# open-bldc-powermini.net
KiCad netlist of a schematic drawn in EAGLE
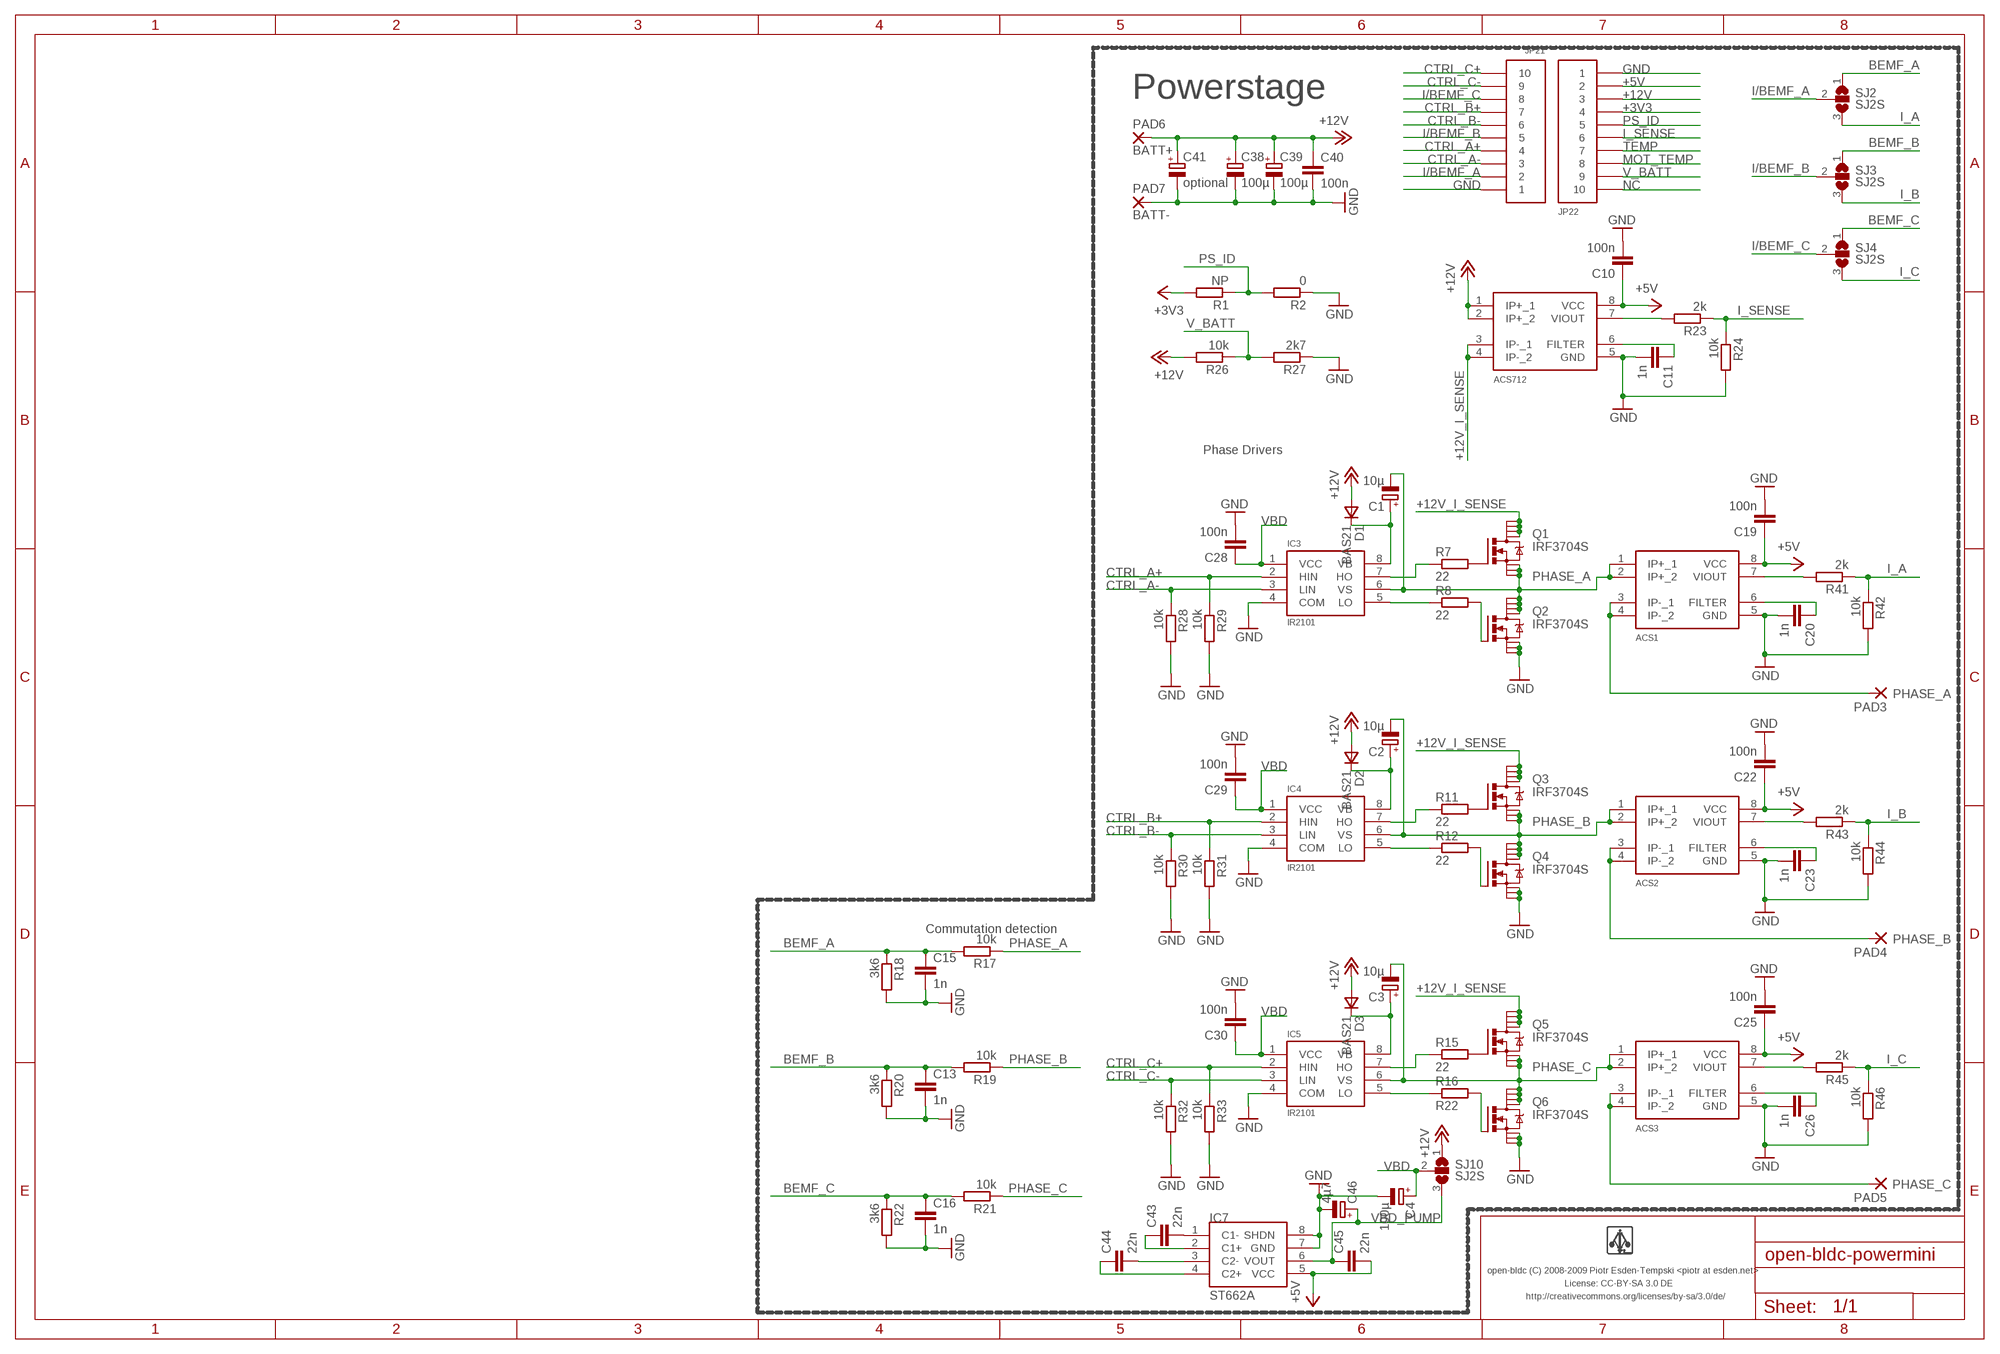
[diagram p0: schematic, sheet 1]

(export (version "E")
  (design (tool "Eeschema 10.0.6"))
  (components
    (comp (ref "ACS1")
      (value "ACS712")
      (footprint "eagle-import:SO8")
      (libsource (lib "eagle-import") (part "ACS712"))
    )
    (comp (ref "ACS2")
      (value "ACS712")
      (footprint "eagle-import:SO8")
      (libsource (lib "eagle-import") (part "ACS712"))
    )
    (comp (ref "ACS3")
      (value "ACS712")
      (footprint "eagle-import:SO8")
      (libsource (lib "eagle-import") (part "ACS712"))
    )
    (comp (ref "ACS712")
      (value "ACS712")
      (footprint "eagle-import:SO8")
      (libsource (lib "eagle-import") (part "ACS712"))
    )
    (comp (ref "C1")
      (value "10µ")
      (footprint "eagle-import:A_3216-18R")
      (libsource (lib "eagle-import") (part "CPOL-EUA/3216-18R"))
    )
    (comp (ref "C2")
      (value "10µ")
      (footprint "eagle-import:A_3216-18R")
      (libsource (lib "eagle-import") (part "CPOL-EUA/3216-18R"))
    )
    (comp (ref "C3")
      (value "10µ")
      (footprint "eagle-import:A_3216-18R")
      (libsource (lib "eagle-import") (part "CPOL-EUA/3216-18R"))
    )
    (comp (ref "C4")
      (value "100µ")
      (footprint "eagle-import:D_7343-31R")
      (libsource (lib "eagle-import") (part "CPOL-EUD/7343-31R"))
    )
    (comp (ref "C10")
      (value "100n")
      (footprint "eagle-import:C0603")
      (libsource (lib "eagle-import") (part "C-EUC0603"))
    )
    (comp (ref "C11")
      (value "1n")
      (footprint "eagle-import:C0603")
      (libsource (lib "eagle-import") (part "C-EUC0603"))
    )
    (comp (ref "C13")
      (value "1n")
      (footprint "eagle-import:C0603")
      (libsource (lib "eagle-import") (part "C-EUC0603"))
    )
    (comp (ref "C15")
      (value "1n")
      (footprint "eagle-import:C0603")
      (libsource (lib "eagle-import") (part "C-EUC0603"))
    )
    (comp (ref "C16")
      (value "1n")
      (footprint "eagle-import:C0603")
      (libsource (lib "eagle-import") (part "C-EUC0603"))
    )
    (comp (ref "C19")
      (value "100n")
      (footprint "eagle-import:C0603")
      (libsource (lib "eagle-import") (part "C-EUC0603"))
    )
    (comp (ref "C20")
      (value "1n")
      (footprint "eagle-import:C0603")
      (libsource (lib "eagle-import") (part "C-EUC0603"))
    )
    (comp (ref "C22")
      (value "100n")
      (footprint "eagle-import:C0603")
      (libsource (lib "eagle-import") (part "C-EUC0603"))
    )
    (comp (ref "C23")
      (value "1n")
      (footprint "eagle-import:C0603")
      (libsource (lib "eagle-import") (part "C-EUC0603"))
    )
    (comp (ref "C25")
      (value "100n")
      (footprint "eagle-import:C0603")
      (libsource (lib "eagle-import") (part "C-EUC0603"))
    )
    (comp (ref "C26")
      (value "1n")
      (footprint "eagle-import:C0603")
      (libsource (lib "eagle-import") (part "C-EUC0603"))
    )
    (comp (ref "C28")
      (value "100n")
      (footprint "eagle-import:C0603")
      (libsource (lib "eagle-import") (part "C-EUC0603"))
    )
    (comp (ref "C29")
      (value "100n")
      (footprint "eagle-import:C0603")
      (libsource (lib "eagle-import") (part "C-EUC0603"))
    )
    (comp (ref "C30")
      (value "100n")
      (footprint "eagle-import:C0603")
      (libsource (lib "eagle-import") (part "C-EUC0603"))
    )
    (comp (ref "C38")
      (value "100µ")
      (footprint "eagle-import:D_7343-31R")
      (libsource (lib "eagle-import") (part "CPOL-EUD/7343-31R"))
    )
    (comp (ref "C39")
      (value "100µ")
      (footprint "eagle-import:D_7343-31R")
      (libsource (lib "eagle-import") (part "CPOL-EUD/7343-31R"))
    )
    (comp (ref "C40")
      (value "100n")
      (footprint "eagle-import:C0603")
      (libsource (lib "eagle-import") (part "C-EUC0603"))
    )
    (comp (ref "C41")
      (value "optional")
      (footprint "eagle-import:E5-6")
      (libsource (lib "eagle-import") (part "CPOL-EUE5-6"))
    )
    (comp (ref "C43")
      (value "22n")
      (footprint "eagle-import:C0603")
      (libsource (lib "eagle-import") (part "C-EUC0603"))
    )
    (comp (ref "C44")
      (value "22n")
      (footprint "eagle-import:C0603")
      (libsource (lib "eagle-import") (part "C-EUC0603"))
    )
    (comp (ref "C45")
      (value "22n")
      (footprint "eagle-import:C0603")
      (libsource (lib "eagle-import") (part "C-EUC0603"))
    )
    (comp (ref "C46")
      (value "4µ7")
      (footprint "eagle-import:A_3216-18R")
      (libsource (lib "eagle-import") (part "CPOL-EUA/3216-18R"))
    )
    (comp (ref "D1")
      (value "BAS21")
      (footprint "eagle-import:SOT-23")
      (libsource (lib "eagle-import") (part "VAR2SOT23"))
    )
    (comp (ref "D2")
      (value "BAS21")
      (footprint "eagle-import:SOT-23")
      (libsource (lib "eagle-import") (part "VAR2SOT23"))
    )
    (comp (ref "D3")
      (value "BAS21")
      (footprint "eagle-import:SOT-23")
      (libsource (lib "eagle-import") (part "VAR2SOT23"))
    )
    (comp (ref "IC3")
      (value "IR2101")
      (footprint "eagle-import:SO-8")
      (libsource (lib "eagle-import") (part "IR2101"))
    )
    (comp (ref "IC4")
      (value "IR2101")
      (footprint "eagle-import:SO-8")
      (libsource (lib "eagle-import") (part "IR2101"))
    )
    (comp (ref "IC5")
      (value "IR2101")
      (footprint "eagle-import:SO-8")
      (libsource (lib "eagle-import") (part "IR2101"))
    )
    (comp (ref "IC7")
      (value "ST662A")
      (footprint "eagle-import:SO8")
      (libsource (lib "eagle-import") (part "ST662A"))
    )
    (comp (ref "JP21")
      (value "PIN_HDR_1.27MM_10")
      (footprint "eagle-import:PIN_HDR_1.27MM_SMD_10")
      (libsource (lib "eagle-import") (part "PIN_HDR_1.27MM_10_SMT"))
    )
    (comp (ref "JP22")
      (value "PIN_HDR_1.27MM_10")
      (footprint "eagle-import:PIN_HDR_1.27MM_SMD_10")
      (libsource (lib "eagle-import") (part "PIN_HDR_1.27MM_10_SMT"))
    )
    (comp (ref "PAD3")
      (value "PHASE_A")
      (footprint "eagle-import:SMD2,54-5,08")
      (libsource (lib "eagle-import") (part "SMD5"))
    )
    (comp (ref "PAD4")
      (value "PHASE_B")
      (footprint "eagle-import:SMD2,54-5,08")
      (libsource (lib "eagle-import") (part "SMD5"))
    )
    (comp (ref "PAD5")
      (value "PHASE_C")
      (footprint "eagle-import:SMD2,54-5,08")
      (libsource (lib "eagle-import") (part "SMD5"))
    )
    (comp (ref "PAD6")
      (value "BATT+")
      (footprint "eagle-import:SMD2,54-5,08")
      (libsource (lib "eagle-import") (part "SMD5"))
    )
    (comp (ref "PAD7")
      (value "BATT-")
      (footprint "eagle-import:SMD2,54-5,08")
      (libsource (lib "eagle-import") (part "SMD5"))
    )
    (comp (ref "Q1")
      (value "IRF3704S")
      (footprint "eagle-import:SO-08")
      (libsource (lib "eagle-import") (part "N-MOSFET-SO8S"))
    )
    (comp (ref "Q2")
      (value "IRF3704S")
      (footprint "eagle-import:SO-08")
      (libsource (lib "eagle-import") (part "N-MOSFET-SO8S"))
    )
    (comp (ref "Q3")
      (value "IRF3704S")
      (footprint "eagle-import:SO-08")
      (libsource (lib "eagle-import") (part "N-MOSFET-SO8S"))
    )
    (comp (ref "Q4")
      (value "IRF3704S")
      (footprint "eagle-import:SO-08")
      (libsource (lib "eagle-import") (part "N-MOSFET-SO8S"))
    )
    (comp (ref "Q5")
      (value "IRF3704S")
      (footprint "eagle-import:SO-08")
      (libsource (lib "eagle-import") (part "N-MOSFET-SO8S"))
    )
    (comp (ref "Q6")
      (value "IRF3704S")
      (footprint "eagle-import:SO-08")
      (libsource (lib "eagle-import") (part "N-MOSFET-SO8S"))
    )
    (comp (ref "R1")
      (value "NP")
      (footprint "eagle-import:R0603")
      (libsource (lib "eagle-import") (part "R-EU_R0603"))
    )
    (comp (ref "R2")
      (value "0")
      (footprint "eagle-import:R0603")
      (libsource (lib "eagle-import") (part "R-EU_R0603"))
    )
    (comp (ref "R7")
      (value "22")
      (footprint "eagle-import:R0603")
      (libsource (lib "eagle-import") (part "R-EU_R0603"))
    )
    (comp (ref "R8")
      (value "22")
      (footprint "eagle-import:R0603")
      (libsource (lib "eagle-import") (part "R-EU_R0603"))
    )
    (comp (ref "R11")
      (value "22")
      (footprint "eagle-import:R0603")
      (libsource (lib "eagle-import") (part "R-EU_R0603"))
    )
    (comp (ref "R12")
      (value "22")
      (footprint "eagle-import:R0603")
      (libsource (lib "eagle-import") (part "R-EU_R0603"))
    )
    (comp (ref "R15")
      (value "22")
      (footprint "eagle-import:R0603")
      (libsource (lib "eagle-import") (part "R-EU_R0603"))
    )
    (comp (ref "R16")
      (value "R22")
      (footprint "eagle-import:R0603")
      (libsource (lib "eagle-import") (part "R-EU_R0603"))
    )
    (comp (ref "R17")
      (value "10k")
      (footprint "eagle-import:R0603")
      (libsource (lib "eagle-import") (part "R-EU_R0603"))
    )
    (comp (ref "R18")
      (value "3k6")
      (footprint "eagle-import:R0603")
      (libsource (lib "eagle-import") (part "R-EU_R0603"))
    )
    (comp (ref "R19")
      (value "10k")
      (footprint "eagle-import:R0603")
      (libsource (lib "eagle-import") (part "R-EU_R0603"))
    )
    (comp (ref "R20")
      (value "3k6")
      (footprint "eagle-import:R0603")
      (libsource (lib "eagle-import") (part "R-EU_R0603"))
    )
    (comp (ref "R21")
      (value "10k")
      (footprint "eagle-import:R0603")
      (libsource (lib "eagle-import") (part "R-EU_R0603"))
    )
    (comp (ref "R22")
      (value "3k6")
      (footprint "eagle-import:R0603")
      (libsource (lib "eagle-import") (part "R-EU_R0603"))
    )
    (comp (ref "R23")
      (value "2k")
      (footprint "eagle-import:R0603")
      (libsource (lib "eagle-import") (part "R-EU_R0603"))
    )
    (comp (ref "R24")
      (value "10k")
      (footprint "eagle-import:R0603")
      (libsource (lib "eagle-import") (part "R-EU_R0603"))
    )
    (comp (ref "R26")
      (value "10k")
      (footprint "eagle-import:R0603")
      (libsource (lib "eagle-import") (part "R-EU_R0603"))
    )
    (comp (ref "R27")
      (value "2k7")
      (footprint "eagle-import:R0603")
      (libsource (lib "eagle-import") (part "R-EU_R0603"))
    )
    (comp (ref "R28")
      (value "10k")
      (footprint "eagle-import:R0603")
      (libsource (lib "eagle-import") (part "R-EU_R0603"))
    )
    (comp (ref "R29")
      (value "10k")
      (footprint "eagle-import:R0603")
      (libsource (lib "eagle-import") (part "R-EU_R0603"))
    )
    (comp (ref "R30")
      (value "10k")
      (footprint "eagle-import:R0603")
      (libsource (lib "eagle-import") (part "R-EU_R0603"))
    )
    (comp (ref "R31")
      (value "10k")
      (footprint "eagle-import:R0603")
      (libsource (lib "eagle-import") (part "R-EU_R0603"))
    )
    (comp (ref "R32")
      (value "10k")
      (footprint "eagle-import:R0603")
      (libsource (lib "eagle-import") (part "R-EU_R0603"))
    )
    (comp (ref "R33")
      (value "10k")
      (footprint "eagle-import:R0603")
      (libsource (lib "eagle-import") (part "R-EU_R0603"))
    )
    (comp (ref "R41")
      (value "2k")
      (footprint "eagle-import:R0603")
      (libsource (lib "eagle-import") (part "R-EU_R0603"))
    )
    (comp (ref "R42")
      (value "10k")
      (footprint "eagle-import:R0603")
      (libsource (lib "eagle-import") (part "R-EU_R0603"))
    )
    (comp (ref "R43")
      (value "2k")
      (footprint "eagle-import:R0603")
      (libsource (lib "eagle-import") (part "R-EU_R0603"))
    )
    (comp (ref "R44")
      (value "10k")
      (footprint "eagle-import:R0603")
      (libsource (lib "eagle-import") (part "R-EU_R0603"))
    )
    (comp (ref "R45")
      (value "2k")
      (footprint "eagle-import:R0603")
      (libsource (lib "eagle-import") (part "R-EU_R0603"))
    )
    (comp (ref "R46")
      (value "10k")
      (footprint "eagle-import:R0603")
      (libsource (lib "eagle-import") (part "R-EU_R0603"))
    )
    (comp (ref "SJ2")
      (value "SJ2S")
      (footprint "eagle-import:SJ2S")
      (libsource (lib "eagle-import") (part "SJ2S"))
    )
    (comp (ref "SJ3")
      (value "SJ2S")
      (footprint "eagle-import:SJ2S")
      (libsource (lib "eagle-import") (part "SJ2S"))
    )
    (comp (ref "SJ4")
      (value "SJ2S")
      (footprint "eagle-import:SJ2S")
      (libsource (lib "eagle-import") (part "SJ2S"))
    )
    (comp (ref "SJ10")
      (value "SJ2S")
      (footprint "eagle-import:SJ2S")
      (libsource (lib "eagle-import") (part "SJ2S"))
    )
  )
  (nets
    (net (code "1") (name "+3V3") (class "Default")
      (node (ref "JP22") (pin "4") (pinfunction "4_4") (pintype "bidirectional"))
      (node (ref "R1") (pin "2") (pinfunction "2_2") (pintype "passive"))
    )
    (net (code "2") (name "+5V") (class "Default")
      (node (ref "ACS1") (pin "8") (pinfunction "VCC_8") (pintype "bidirectional"))
      (node (ref "ACS2") (pin "8") (pinfunction "VCC_8") (pintype "bidirectional"))
      (node (ref "ACS3") (pin "8") (pinfunction "VCC_8") (pintype "bidirectional"))
      (node (ref "ACS712") (pin "8") (pinfunction "VCC_8") (pintype "bidirectional"))
      (node (ref "C10") (pin "1") (pinfunction "1_1") (pintype "passive"))
      (node (ref "C19") (pin "1") (pinfunction "1_1") (pintype "passive"))
      (node (ref "C22") (pin "1") (pinfunction "1_1") (pintype "passive"))
      (node (ref "C25") (pin "1") (pinfunction "1_1") (pintype "passive"))
      (node (ref "C45") (pin "2") (pinfunction "2_2") (pintype "passive"))
      (node (ref "IC7") (pin "5") (pinfunction "VCC_5") (pintype "bidirectional"))
      (node (ref "JP22") (pin "2") (pinfunction "2_2") (pintype "bidirectional"))
    )
    (net (code "3") (name "+12V") (class "Default")
      (node (ref "ACS712") (pin "1") (pinfunction "IP+_1_1") (pintype "bidirectional"))
      (node (ref "ACS712") (pin "2") (pinfunction "IP+_2_2") (pintype "bidirectional"))
      (node (ref "C38") (pin "+") (pinfunction "+_+") (pintype "passive"))
      (node (ref "C39") (pin "+") (pinfunction "+_+") (pintype "passive"))
      (node (ref "C40") (pin "1") (pinfunction "1_1") (pintype "passive"))
      (node (ref "C41") (pin "+") (pinfunction "+_+") (pintype "passive"))
      (node (ref "D1") (pin "3") (pinfunction "A_3") (pintype "passive"))
      (node (ref "D2") (pin "3") (pinfunction "A_3") (pintype "passive"))
      (node (ref "D3") (pin "3") (pinfunction "A_3") (pintype "passive"))
      (node (ref "JP22") (pin "3") (pinfunction "3_3") (pintype "bidirectional"))
      (node (ref "PAD6") (pin "1") (pinfunction "P_1") (pintype "passive"))
      (node (ref "R26") (pin "2") (pinfunction "2_2") (pintype "passive"))
      (node (ref "SJ10") (pin "1") (pinfunction "1_1") (pintype "passive"))
    )
    (net (code "4") (name "/+12V_I_SENSE") (class "Default")
      (node (ref "ACS712") (pin "3") (pinfunction "IP-_1_3") (pintype "bidirectional"))
      (node (ref "ACS712") (pin "4") (pinfunction "IP-_2_4") (pintype "bidirectional"))
      (node (ref "Q1") (pin "5") (pinfunction "D_5") (pintype "passive"))
      (node (ref "Q1") (pin "6") (pinfunction "D_6") (pintype "passive"))
      (node (ref "Q1") (pin "7") (pinfunction "D_7") (pintype "passive"))
      (node (ref "Q1") (pin "8") (pinfunction "D_8") (pintype "passive"))
      (node (ref "Q3") (pin "5") (pinfunction "D_5") (pintype "passive"))
      (node (ref "Q3") (pin "6") (pinfunction "D_6") (pintype "passive"))
      (node (ref "Q3") (pin "7") (pinfunction "D_7") (pintype "passive"))
      (node (ref "Q3") (pin "8") (pinfunction "D_8") (pintype "passive"))
      (node (ref "Q5") (pin "5") (pinfunction "D_5") (pintype "passive"))
      (node (ref "Q5") (pin "6") (pinfunction "D_6") (pintype "passive"))
      (node (ref "Q5") (pin "7") (pinfunction "D_7") (pintype "passive"))
      (node (ref "Q5") (pin "8") (pinfunction "D_8") (pintype "passive"))
    )
    (net (code "5") (name "/BEMF_A") (class "Default")
      (node (ref "C15") (pin "1") (pinfunction "1_1") (pintype "passive"))
      (node (ref "R17") (pin "2") (pinfunction "2_2") (pintype "passive"))
      (node (ref "R18") (pin "1") (pinfunction "1_1") (pintype "passive"))
      (node (ref "SJ2") (pin "1") (pinfunction "1_1") (pintype "passive"))
    )
    (net (code "6") (name "/BEMF_B") (class "Default")
      (node (ref "C13") (pin "1") (pinfunction "1_1") (pintype "passive"))
      (node (ref "R19") (pin "2") (pinfunction "2_2") (pintype "passive"))
      (node (ref "R20") (pin "1") (pinfunction "1_1") (pintype "passive"))
      (node (ref "SJ3") (pin "1") (pinfunction "1_1") (pintype "passive"))
    )
    (net (code "7") (name "/BEMF_C") (class "Default")
      (node (ref "C16") (pin "1") (pinfunction "1_1") (pintype "passive"))
      (node (ref "R21") (pin "2") (pinfunction "2_2") (pintype "passive"))
      (node (ref "R22") (pin "1") (pinfunction "1_1") (pintype "passive"))
      (node (ref "SJ4") (pin "1") (pinfunction "1_1") (pintype "passive"))
    )
    (net (code "8") (name "/CTRL_A+") (class "Default")
      (node (ref "IC3") (pin "2") (pinfunction "HIN_2") (pintype "bidirectional"))
      (node (ref "JP21") (pin "4") (pinfunction "4_4") (pintype "bidirectional"))
      (node (ref "R29") (pin "1") (pinfunction "1_1") (pintype "passive"))
    )
    (net (code "9") (name "/CTRL_A-") (class "Default")
      (node (ref "IC3") (pin "3") (pinfunction "LIN_3") (pintype "bidirectional"))
      (node (ref "JP21") (pin "3") (pinfunction "3_3") (pintype "bidirectional"))
      (node (ref "R28") (pin "1") (pinfunction "1_1") (pintype "passive"))
    )
    (net (code "10") (name "/CTRL_B+") (class "Default")
      (node (ref "IC4") (pin "2") (pinfunction "HIN_2") (pintype "bidirectional"))
      (node (ref "JP21") (pin "7") (pinfunction "7_7") (pintype "bidirectional"))
      (node (ref "R31") (pin "1") (pinfunction "1_1") (pintype "passive"))
    )
    (net (code "11") (name "/CTRL_B-") (class "Default")
      (node (ref "IC4") (pin "3") (pinfunction "LIN_3") (pintype "bidirectional"))
      (node (ref "JP21") (pin "6") (pinfunction "6_6") (pintype "bidirectional"))
      (node (ref "R30") (pin "1") (pinfunction "1_1") (pintype "passive"))
    )
    (net (code "12") (name "/CTRL_C+") (class "Default")
      (node (ref "IC5") (pin "2") (pinfunction "HIN_2") (pintype "bidirectional"))
      (node (ref "JP21") (pin "10") (pinfunction "10_10") (pintype "bidirectional"))
      (node (ref "R33") (pin "1") (pinfunction "1_1") (pintype "passive"))
    )
    (net (code "13") (name "/CTRL_C-") (class "Default")
      (node (ref "IC5") (pin "3") (pinfunction "LIN_3") (pintype "bidirectional"))
      (node (ref "JP21") (pin "9") (pinfunction "9_9") (pintype "bidirectional"))
      (node (ref "R32") (pin "1") (pinfunction "1_1") (pintype "passive"))
    )
    (net (code "14") (name "/I_A") (class "Default")
      (node (ref "R41") (pin "1") (pinfunction "1_1") (pintype "passive"))
      (node (ref "R42") (pin "1") (pinfunction "1_1") (pintype "passive"))
      (node (ref "SJ2") (pin "3") (pinfunction "3_3") (pintype "passive"))
    )
    (net (code "15") (name "/I_B") (class "Default")
      (node (ref "R43") (pin "1") (pinfunction "1_1") (pintype "passive"))
      (node (ref "R44") (pin "1") (pinfunction "1_1") (pintype "passive"))
      (node (ref "SJ3") (pin "3") (pinfunction "3_3") (pintype "passive"))
    )
    (net (code "16") (name "/I_C") (class "Default")
      (node (ref "R45") (pin "1") (pinfunction "1_1") (pintype "passive"))
      (node (ref "R46") (pin "1") (pinfunction "1_1") (pintype "passive"))
      (node (ref "SJ4") (pin "3") (pinfunction "3_3") (pintype "passive"))
    )
    (net (code "17") (name "/I_SENSE") (class "Default")
      (node (ref "JP22") (pin "6") (pinfunction "6_6") (pintype "bidirectional"))
      (node (ref "R23") (pin "1") (pinfunction "1_1") (pintype "passive"))
      (node (ref "R24") (pin "1") (pinfunction "1_1") (pintype "passive"))
    )
    (net (code "18") (name "/I{slash}BEMF_A") (class "Default")
      (node (ref "JP21") (pin "2") (pinfunction "2_2") (pintype "bidirectional"))
      (node (ref "SJ2") (pin "2") (pinfunction "2_2") (pintype "passive"))
    )
    (net (code "19") (name "/I{slash}BEMF_B") (class "Default")
      (node (ref "JP21") (pin "5") (pinfunction "5_5") (pintype "bidirectional"))
      (node (ref "SJ3") (pin "2") (pinfunction "2_2") (pintype "passive"))
    )
    (net (code "20") (name "/I{slash}BEMF_C") (class "Default")
      (node (ref "JP21") (pin "8") (pinfunction "8_8") (pintype "bidirectional"))
      (node (ref "SJ4") (pin "2") (pinfunction "2_2") (pintype "passive"))
    )
    (net (code "21") (name "/MOT_TEMP") (class "Default")
      (node (ref "JP22") (pin "8") (pinfunction "8_8") (pintype "bidirectional"))
    )
    (net (code "22") (name "/NC") (class "Default")
      (node (ref "JP22") (pin "10") (pinfunction "10_10") (pintype "bidirectional"))
    )
    (net (code "23") (name "/PHASE_A") (class "Default")
      (node (ref "ACS1") (pin "1") (pinfunction "IP+_1_1") (pintype "bidirectional"))
      (node (ref "ACS1") (pin "2") (pinfunction "IP+_2_2") (pintype "bidirectional"))
      (node (ref "C1") (pin "-") (pinfunction "-_-") (pintype "passive"))
      (node (ref "IC3") (pin "6") (pinfunction "VS_6") (pintype "bidirectional"))
      (node (ref "Q1") (pin "1") (pinfunction "S_1") (pintype "passive"))
      (node (ref "Q1") (pin "2") (pinfunction "S_2") (pintype "passive"))
      (node (ref "Q1") (pin "3") (pinfunction "S_3") (pintype "passive"))
      (node (ref "Q2") (pin "5") (pinfunction "D_5") (pintype "passive"))
      (node (ref "Q2") (pin "6") (pinfunction "D_6") (pintype "passive"))
      (node (ref "Q2") (pin "7") (pinfunction "D_7") (pintype "passive"))
      (node (ref "Q2") (pin "8") (pinfunction "D_8") (pintype "passive"))
      (node (ref "R17") (pin "1") (pinfunction "1_1") (pintype "passive"))
    )
    (net (code "24") (name "/PHASE_B") (class "Default")
      (node (ref "ACS2") (pin "1") (pinfunction "IP+_1_1") (pintype "bidirectional"))
      (node (ref "ACS2") (pin "2") (pinfunction "IP+_2_2") (pintype "bidirectional"))
      (node (ref "C2") (pin "-") (pinfunction "-_-") (pintype "passive"))
      (node (ref "IC4") (pin "6") (pinfunction "VS_6") (pintype "bidirectional"))
      (node (ref "Q3") (pin "1") (pinfunction "S_1") (pintype "passive"))
      (node (ref "Q3") (pin "2") (pinfunction "S_2") (pintype "passive"))
      (node (ref "Q3") (pin "3") (pinfunction "S_3") (pintype "passive"))
      (node (ref "Q4") (pin "5") (pinfunction "D_5") (pintype "passive"))
      (node (ref "Q4") (pin "6") (pinfunction "D_6") (pintype "passive"))
      (node (ref "Q4") (pin "7") (pinfunction "D_7") (pintype "passive"))
      (node (ref "Q4") (pin "8") (pinfunction "D_8") (pintype "passive"))
      (node (ref "R19") (pin "1") (pinfunction "1_1") (pintype "passive"))
    )
    (net (code "25") (name "/PHASE_C") (class "Default")
      (node (ref "ACS3") (pin "1") (pinfunction "IP+_1_1") (pintype "bidirectional"))
      (node (ref "ACS3") (pin "2") (pinfunction "IP+_2_2") (pintype "bidirectional"))
      (node (ref "C3") (pin "-") (pinfunction "-_-") (pintype "passive"))
      (node (ref "IC5") (pin "6") (pinfunction "VS_6") (pintype "bidirectional"))
      (node (ref "Q5") (pin "1") (pinfunction "S_1") (pintype "passive"))
      (node (ref "Q5") (pin "2") (pinfunction "S_2") (pintype "passive"))
      (node (ref "Q5") (pin "3") (pinfunction "S_3") (pintype "passive"))
      (node (ref "Q6") (pin "5") (pinfunction "D_5") (pintype "passive"))
      (node (ref "Q6") (pin "6") (pinfunction "D_6") (pintype "passive"))
      (node (ref "Q6") (pin "7") (pinfunction "D_7") (pintype "passive"))
      (node (ref "Q6") (pin "8") (pinfunction "D_8") (pintype "passive"))
      (node (ref "R21") (pin "1") (pinfunction "1_1") (pintype "passive"))
    )
    (net (code "26") (name "/PS_ID") (class "Default")
      (node (ref "JP22") (pin "5") (pinfunction "5_5") (pintype "bidirectional"))
      (node (ref "R1") (pin "1") (pinfunction "1_1") (pintype "passive"))
      (node (ref "R2") (pin "2") (pinfunction "2_2") (pintype "passive"))
    )
    (net (code "27") (name "/TEMP") (class "Default")
      (node (ref "JP22") (pin "7") (pinfunction "7_7") (pintype "bidirectional"))
    )
    (net (code "28") (name "/VBD") (class "Default")
      (node (ref "C28") (pin "1") (pinfunction "1_1") (pintype "passive"))
      (node (ref "C29") (pin "1") (pinfunction "1_1") (pintype "passive"))
      (node (ref "C30") (pin "1") (pinfunction "1_1") (pintype "passive"))
      (node (ref "C4") (pin "+") (pinfunction "+_+") (pintype "passive"))
      (node (ref "IC3") (pin "1") (pinfunction "VCC_1") (pintype "bidirectional"))
      (node (ref "IC4") (pin "1") (pinfunction "VCC_1") (pintype "bidirectional"))
      (node (ref "IC5") (pin "1") (pinfunction "VCC_1") (pintype "bidirectional"))
      (node (ref "SJ10") (pin "2") (pinfunction "2_2") (pintype "passive"))
    )
    (net (code "29") (name "/VBD_PUMP") (class "Default")
      (node (ref "C45") (pin "1") (pinfunction "1_1") (pintype "passive"))
      (node (ref "C46") (pin "+") (pinfunction "+_+") (pintype "passive"))
      (node (ref "IC7") (pin "6") (pinfunction "VOUT_6") (pintype "bidirectional"))
      (node (ref "SJ10") (pin "3") (pinfunction "3_3") (pintype "passive"))
    )
    (net (code "30") (name "/V_BATT") (class "Default")
      (node (ref "JP22") (pin "9") (pinfunction "9_9") (pintype "bidirectional"))
      (node (ref "R26") (pin "1") (pinfunction "1_1") (pintype "passive"))
      (node (ref "R27") (pin "2") (pinfunction "2_2") (pintype "passive"))
    )
    (net (code "31") (name "GND") (class "Default")
      (node (ref "ACS1") (pin "5") (pinfunction "GND_5") (pintype "bidirectional"))
      (node (ref "ACS2") (pin "5") (pinfunction "GND_5") (pintype "bidirectional"))
      (node (ref "ACS3") (pin "5") (pinfunction "GND_5") (pintype "bidirectional"))
      (node (ref "ACS712") (pin "5") (pinfunction "GND_5") (pintype "bidirectional"))
      (node (ref "C10") (pin "2") (pinfunction "2_2") (pintype "passive"))
      (node (ref "C11") (pin "2") (pinfunction "2_2") (pintype "passive"))
      (node (ref "C13") (pin "2") (pinfunction "2_2") (pintype "passive"))
      (node (ref "C15") (pin "2") (pinfunction "2_2") (pintype "passive"))
      (node (ref "C16") (pin "2") (pinfunction "2_2") (pintype "passive"))
      (node (ref "C19") (pin "2") (pinfunction "2_2") (pintype "passive"))
      (node (ref "C20") (pin "2") (pinfunction "2_2") (pintype "passive"))
      (node (ref "C22") (pin "2") (pinfunction "2_2") (pintype "passive"))
      (node (ref "C23") (pin "2") (pinfunction "2_2") (pintype "passive"))
      (node (ref "C25") (pin "2") (pinfunction "2_2") (pintype "passive"))
      (node (ref "C26") (pin "2") (pinfunction "2_2") (pintype "passive"))
      (node (ref "C28") (pin "2") (pinfunction "2_2") (pintype "passive"))
      (node (ref "C29") (pin "2") (pinfunction "2_2") (pintype "passive"))
      (node (ref "C30") (pin "2") (pinfunction "2_2") (pintype "passive"))
      (node (ref "C38") (pin "-") (pinfunction "-_-") (pintype "passive"))
      (node (ref "C39") (pin "-") (pinfunction "-_-") (pintype "passive"))
      (node (ref "C4") (pin "-") (pinfunction "-_-") (pintype "passive"))
      (node (ref "C40") (pin "2") (pinfunction "2_2") (pintype "passive"))
      (node (ref "C41") (pin "-") (pinfunction "-_-") (pintype "passive"))
      (node (ref "C46") (pin "-") (pinfunction "-_-") (pintype "passive"))
      (node (ref "IC3") (pin "4") (pinfunction "COM_4") (pintype "bidirectional"))
      (node (ref "IC4") (pin "4") (pinfunction "COM_4") (pintype "bidirectional"))
      (node (ref "IC5") (pin "4") (pinfunction "COM_4") (pintype "bidirectional"))
      (node (ref "IC7") (pin "7") (pinfunction "GND_7") (pintype "bidirectional"))
      (node (ref "IC7") (pin "8") (pinfunction "SHDN_8") (pintype "bidirectional"))
      (node (ref "JP21") (pin "1") (pinfunction "1_1") (pintype "bidirectional"))
      (node (ref "JP22") (pin "1") (pinfunction "1_1") (pintype "bidirectional"))
      (node (ref "PAD7") (pin "1") (pinfunction "P_1") (pintype "passive"))
      (node (ref "Q2") (pin "1") (pinfunction "S_1") (pintype "passive"))
      (node (ref "Q2") (pin "2") (pinfunction "S_2") (pintype "passive"))
      (node (ref "Q2") (pin "3") (pinfunction "S_3") (pintype "passive"))
      (node (ref "Q4") (pin "1") (pinfunction "S_1") (pintype "passive"))
      (node (ref "Q4") (pin "2") (pinfunction "S_2") (pintype "passive"))
      (node (ref "Q4") (pin "3") (pinfunction "S_3") (pintype "passive"))
      (node (ref "Q6") (pin "1") (pinfunction "S_1") (pintype "passive"))
      (node (ref "Q6") (pin "2") (pinfunction "S_2") (pintype "passive"))
      (node (ref "Q6") (pin "3") (pinfunction "S_3") (pintype "passive"))
      (node (ref "R18") (pin "2") (pinfunction "2_2") (pintype "passive"))
      (node (ref "R2") (pin "1") (pinfunction "1_1") (pintype "passive"))
      (node (ref "R20") (pin "2") (pinfunction "2_2") (pintype "passive"))
      (node (ref "R22") (pin "2") (pinfunction "2_2") (pintype "passive"))
      (node (ref "R24") (pin "2") (pinfunction "2_2") (pintype "passive"))
      (node (ref "R27") (pin "1") (pinfunction "1_1") (pintype "passive"))
      (node (ref "R28") (pin "2") (pinfunction "2_2") (pintype "passive"))
      (node (ref "R29") (pin "2") (pinfunction "2_2") (pintype "passive"))
      (node (ref "R30") (pin "2") (pinfunction "2_2") (pintype "passive"))
      (node (ref "R31") (pin "2") (pinfunction "2_2") (pintype "passive"))
      (node (ref "R32") (pin "2") (pinfunction "2_2") (pintype "passive"))
      (node (ref "R33") (pin "2") (pinfunction "2_2") (pintype "passive"))
      (node (ref "R42") (pin "2") (pinfunction "2_2") (pintype "passive"))
      (node (ref "R44") (pin "2") (pinfunction "2_2") (pintype "passive"))
      (node (ref "R46") (pin "2") (pinfunction "2_2") (pintype "passive"))
    )
    (net (code "32") (name "Net-(ACS1-FILTER)") (class "Default")
      (node (ref "ACS1") (pin "6") (pinfunction "FILTER_6") (pintype "bidirectional"))
      (node (ref "C20") (pin "1") (pinfunction "1_1") (pintype "passive"))
    )
    (net (code "33") (name "Net-(ACS1-IP-_1)") (class "Default")
      (node (ref "ACS1") (pin "3") (pinfunction "IP-_1_3") (pintype "bidirectional"))
      (node (ref "ACS1") (pin "4") (pinfunction "IP-_2_4") (pintype "bidirectional"))
      (node (ref "PAD3") (pin "1") (pinfunction "P_1") (pintype "passive"))
    )
    (net (code "34") (name "Net-(ACS1-VIOUT)") (class "Default")
      (node (ref "ACS1") (pin "7") (pinfunction "VIOUT_7") (pintype "bidirectional"))
      (node (ref "R41") (pin "2") (pinfunction "2_2") (pintype "passive"))
    )
    (net (code "35") (name "Net-(ACS2-FILTER)") (class "Default")
      (node (ref "ACS2") (pin "6") (pinfunction "FILTER_6") (pintype "bidirectional"))
      (node (ref "C23") (pin "1") (pinfunction "1_1") (pintype "passive"))
    )
    (net (code "36") (name "Net-(ACS2-IP-_1)") (class "Default")
      (node (ref "ACS2") (pin "3") (pinfunction "IP-_1_3") (pintype "bidirectional"))
      (node (ref "ACS2") (pin "4") (pinfunction "IP-_2_4") (pintype "bidirectional"))
      (node (ref "PAD4") (pin "1") (pinfunction "P_1") (pintype "passive"))
    )
    (net (code "37") (name "Net-(ACS2-VIOUT)") (class "Default")
      (node (ref "ACS2") (pin "7") (pinfunction "VIOUT_7") (pintype "bidirectional"))
      (node (ref "R43") (pin "2") (pinfunction "2_2") (pintype "passive"))
    )
    (net (code "38") (name "Net-(ACS3-FILTER)") (class "Default")
      (node (ref "ACS3") (pin "6") (pinfunction "FILTER_6") (pintype "bidirectional"))
      (node (ref "C26") (pin "1") (pinfunction "1_1") (pintype "passive"))
    )
    (net (code "39") (name "Net-(ACS3-IP-_1)") (class "Default")
      (node (ref "ACS3") (pin "3") (pinfunction "IP-_1_3") (pintype "bidirectional"))
      (node (ref "ACS3") (pin "4") (pinfunction "IP-_2_4") (pintype "bidirectional"))
      (node (ref "PAD5") (pin "1") (pinfunction "P_1") (pintype "passive"))
    )
    (net (code "40") (name "Net-(ACS3-VIOUT)") (class "Default")
      (node (ref "ACS3") (pin "7") (pinfunction "VIOUT_7") (pintype "bidirectional"))
      (node (ref "R45") (pin "2") (pinfunction "2_2") (pintype "passive"))
    )
    (net (code "41") (name "Net-(ACS712-FILTER)") (class "Default")
      (node (ref "ACS712") (pin "6") (pinfunction "FILTER_6") (pintype "bidirectional"))
      (node (ref "C11") (pin "1") (pinfunction "1_1") (pintype "passive"))
    )
    (net (code "42") (name "Net-(ACS712-VIOUT)") (class "Default")
      (node (ref "ACS712") (pin "7") (pinfunction "VIOUT_7") (pintype "bidirectional"))
      (node (ref "R23") (pin "2") (pinfunction "2_2") (pintype "passive"))
    )
    (net (code "43") (name "Net-(D1-C)") (class "Default")
      (node (ref "C1") (pin "+") (pinfunction "+_+") (pintype "passive"))
      (node (ref "D1") (pin "1") (pinfunction "C_1") (pintype "passive"))
      (node (ref "IC3") (pin "8") (pinfunction "VB_8") (pintype "bidirectional"))
    )
    (net (code "44") (name "Net-(D2-C)") (class "Default")
      (node (ref "C2") (pin "+") (pinfunction "+_+") (pintype "passive"))
      (node (ref "D2") (pin "1") (pinfunction "C_1") (pintype "passive"))
      (node (ref "IC4") (pin "8") (pinfunction "VB_8") (pintype "bidirectional"))
    )
    (net (code "45") (name "Net-(D3-C)") (class "Default")
      (node (ref "C3") (pin "+") (pinfunction "+_+") (pintype "passive"))
      (node (ref "D3") (pin "1") (pinfunction "C_1") (pintype "passive"))
      (node (ref "IC5") (pin "8") (pinfunction "VB_8") (pintype "bidirectional"))
    )
    (net (code "46") (name "Net-(IC3-HO)") (class "Default")
      (node (ref "IC3") (pin "7") (pinfunction "HO_7") (pintype "bidirectional"))
      (node (ref "R7") (pin "1") (pinfunction "1_1") (pintype "passive"))
    )
    (net (code "47") (name "Net-(IC3-LO)") (class "Default")
      (node (ref "IC3") (pin "5") (pinfunction "LO_5") (pintype "bidirectional"))
      (node (ref "R8") (pin "1") (pinfunction "1_1") (pintype "passive"))
    )
    (net (code "48") (name "Net-(IC4-HO)") (class "Default")
      (node (ref "IC4") (pin "7") (pinfunction "HO_7") (pintype "bidirectional"))
      (node (ref "R11") (pin "1") (pinfunction "1_1") (pintype "passive"))
    )
    (net (code "49") (name "Net-(IC4-LO)") (class "Default")
      (node (ref "IC4") (pin "5") (pinfunction "LO_5") (pintype "bidirectional"))
      (node (ref "R12") (pin "1") (pinfunction "1_1") (pintype "passive"))
    )
    (net (code "50") (name "Net-(IC5-HO)") (class "Default")
      (node (ref "IC5") (pin "7") (pinfunction "HO_7") (pintype "bidirectional"))
      (node (ref "R15") (pin "1") (pinfunction "1_1") (pintype "passive"))
    )
    (net (code "51") (name "Net-(IC5-LO)") (class "Default")
      (node (ref "IC5") (pin "5") (pinfunction "LO_5") (pintype "bidirectional"))
      (node (ref "R16") (pin "1") (pinfunction "1_1") (pintype "passive"))
    )
    (net (code "52") (name "Net-(IC7-C1+)") (class "Default")
      (node (ref "C43") (pin "1") (pinfunction "1_1") (pintype "passive"))
      (node (ref "IC7") (pin "2") (pinfunction "C1+_2") (pintype "bidirectional"))
    )
    (net (code "53") (name "Net-(IC7-C1-)") (class "Default")
      (node (ref "C43") (pin "2") (pinfunction "2_2") (pintype "passive"))
      (node (ref "IC7") (pin "1") (pinfunction "C1-_1") (pintype "bidirectional"))
    )
    (net (code "54") (name "Net-(IC7-C2+)") (class "Default")
      (node (ref "C44") (pin "1") (pinfunction "1_1") (pintype "passive"))
      (node (ref "IC7") (pin "4") (pinfunction "C2+_4") (pintype "bidirectional"))
    )
    (net (code "55") (name "Net-(IC7-C2-)") (class "Default")
      (node (ref "C44") (pin "2") (pinfunction "2_2") (pintype "passive"))
      (node (ref "IC7") (pin "3") (pinfunction "C2-_3") (pintype "bidirectional"))
    )
    (net (code "56") (name "Net-(Q1-G)") (class "Default")
      (node (ref "Q1") (pin "4") (pinfunction "G_4") (pintype "passive"))
      (node (ref "R7") (pin "2") (pinfunction "2_2") (pintype "passive"))
    )
    (net (code "57") (name "Net-(Q2-G)") (class "Default")
      (node (ref "Q2") (pin "4") (pinfunction "G_4") (pintype "passive"))
      (node (ref "R8") (pin "2") (pinfunction "2_2") (pintype "passive"))
    )
    (net (code "58") (name "Net-(Q3-G)") (class "Default")
      (node (ref "Q3") (pin "4") (pinfunction "G_4") (pintype "passive"))
      (node (ref "R11") (pin "2") (pinfunction "2_2") (pintype "passive"))
    )
    (net (code "59") (name "Net-(Q4-G)") (class "Default")
      (node (ref "Q4") (pin "4") (pinfunction "G_4") (pintype "passive"))
      (node (ref "R12") (pin "2") (pinfunction "2_2") (pintype "passive"))
    )
    (net (code "60") (name "Net-(Q5-G)") (class "Default")
      (node (ref "Q5") (pin "4") (pinfunction "G_4") (pintype "passive"))
      (node (ref "R15") (pin "2") (pinfunction "2_2") (pintype "passive"))
    )
    (net (code "61") (name "Net-(Q6-G)") (class "Default")
      (node (ref "Q6") (pin "4") (pinfunction "G_4") (pintype "passive"))
      (node (ref "R16") (pin "2") (pinfunction "2_2") (pintype "passive"))
    )
  )
)
